# RefOsc10MHz_1V3.net
KiCad netlist of a schematic drawn in EAGLE
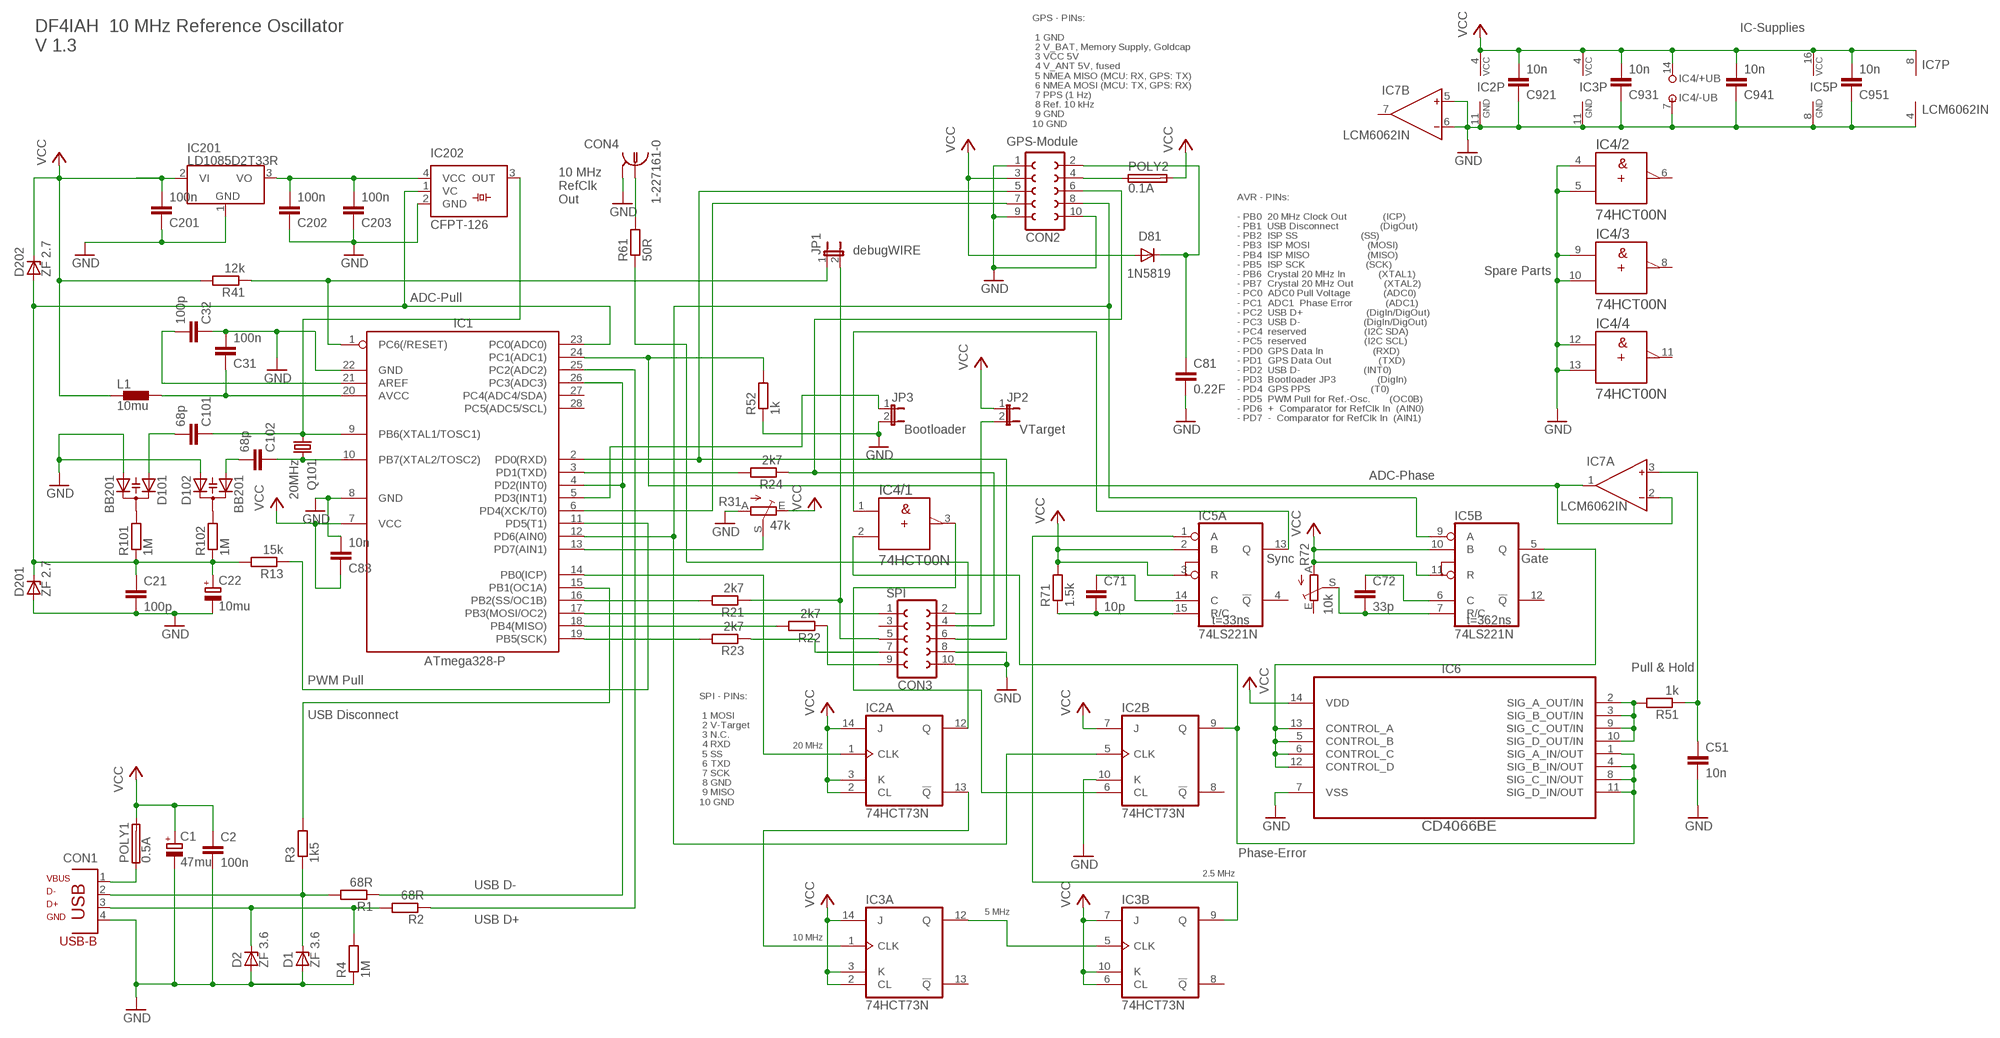
[diagram p0: schematic, sheet 1]

(export (version "E")
  (design (tool "Eeschema 10.0.6"))
  (components
    (comp (ref "C1")
      (value "47mu")
      (footprint "eagle-import:E2-4")
      (libsource (lib "eagle-import") (part "CPOL-EUE2-4"))
    )
    (comp (ref "C2")
      (value "100n")
      (footprint "eagle-import:C5B3")
      (libsource (lib "eagle-import") (part "C5/3"))
    )
    (comp (ref "C21")
      (value "100p")
      (footprint "eagle-import:C5B3")
      (libsource (lib "eagle-import") (part "C5/3"))
    )
    (comp (ref "C22")
      (value "10mu")
      (footprint "eagle-import:E2-4")
      (libsource (lib "eagle-import") (part "CPOL-EUE2-4"))
    )
    (comp (ref "C31")
      (value "100n")
      (footprint "eagle-import:C5B3")
      (libsource (lib "eagle-import") (part "C5/3"))
    )
    (comp (ref "C32")
      (value "100p")
      (footprint "eagle-import:C5B3")
      (libsource (lib "eagle-import") (part "C5/3"))
    )
    (comp (ref "C51")
      (value "10n")
      (footprint "eagle-import:C5B3")
      (libsource (lib "eagle-import") (part "C5/3"))
    )
    (comp (ref "C71")
      (value "10p")
      (footprint "eagle-import:C5B3")
      (libsource (lib "eagle-import") (part "C5/3"))
    )
    (comp (ref "C72")
      (value "33p")
      (footprint "eagle-import:C5B3")
      (libsource (lib "eagle-import") (part "C5/3"))
    )
    (comp (ref "C81")
      (value "0.22F")
      (footprint "eagle-import:C5B7.2")
      (libsource (lib "eagle-import") (part "C5/7.2"))
    )
    (comp (ref "C83")
      (value "10n")
      (footprint "eagle-import:C5B3")
      (libsource (lib "eagle-import") (part "C5/3"))
    )
    (comp (ref "C101")
      (value "68p")
      (footprint "eagle-import:C5B3")
      (libsource (lib "eagle-import") (part "C5/3"))
    )
    (comp (ref "C102")
      (value "68p")
      (footprint "eagle-import:C5B3")
      (libsource (lib "eagle-import") (part "C5/3"))
    )
    (comp (ref "C201")
      (value "100n")
      (footprint "eagle-import:C5B3")
      (libsource (lib "eagle-import") (part "C5/3"))
    )
    (comp (ref "C202")
      (value "100n")
      (footprint "eagle-import:C5B3")
      (libsource (lib "eagle-import") (part "C5/3"))
    )
    (comp (ref "C203")
      (value "100n")
      (footprint "eagle-import:C5B3")
      (libsource (lib "eagle-import") (part "C5/3"))
    )
    (comp (ref "C921")
      (value "10n")
      (footprint "eagle-import:C5B3")
      (libsource (lib "eagle-import") (part "C5/3"))
    )
    (comp (ref "C931")
      (value "10n")
      (footprint "eagle-import:C5B3")
      (libsource (lib "eagle-import") (part "C5/3"))
    )
    (comp (ref "C941")
      (value "10n")
      (footprint "eagle-import:C5B3")
      (libsource (lib "eagle-import") (part "C5/3"))
    )
    (comp (ref "C951")
      (value "10n")
      (footprint "eagle-import:C5B3")
      (libsource (lib "eagle-import") (part "C5/3"))
    )
    (comp (ref "CON1")
      (value "PN61729")
      (footprint "eagle-import:PN61729")
      (libsource (lib "eagle-import") (part "PN61729"))
    )
    (comp (ref "CON2")
      (value "FE05-2")
      (footprint "eagle-import:FE05-2")
      (libsource (lib "eagle-import") (part "FE05-2"))
    )
    (comp (ref "CON3")
      (value "FE05-2")
      (footprint "eagle-import:FE05-2")
      (libsource (lib "eagle-import") (part "FE05-2"))
    )
    (comp (ref "CON4")
      (value "1-227161-0")
      (footprint "eagle-import:AMP_227161")
      (fields (field (name "MF") "TYCO ELECTRONICS") (field (name "MPN") "1-227161"))
      (libsource (lib "eagle-import") (part "?2271611--0"))
    )
    (comp (ref "D1")
      (value "ZF 3.6")
      (footprint "eagle-import:DO41Z10")
      (libsource (lib "eagle-import") (part "1N4728"))
    )
    (comp (ref "D2")
      (value "ZF 3.6")
      (footprint "eagle-import:DO41Z10")
      (libsource (lib "eagle-import") (part "1N4728"))
    )
    (comp (ref "D81")
      (value "1N5819")
      (footprint "eagle-import:DO41-10")
      (libsource (lib "eagle-import") (part "1N4942"))
    )
    (comp (ref "D101")
      (value "BB201")
      (footprint "eagle-import:SOT23")
      (libsource (lib "eagle-import") (part "BBY51"))
    )
    (comp (ref "D102")
      (value "BB201")
      (footprint "eagle-import:SOT23")
      (libsource (lib "eagle-import") (part "BBY51"))
    )
    (comp (ref "D201")
      (value "ZF 2.7")
      (footprint "eagle-import:DO41Z10")
      (libsource (lib "eagle-import") (part "1N4728"))
    )
    (comp (ref "D202")
      (value "ZF 2.7")
      (footprint "eagle-import:DO41Z10")
      (libsource (lib "eagle-import") (part "1N4728"))
    )
    (comp (ref "IC1")
      (value "ATmega328-P")
      (footprint "eagle-import:DIL28-3")
      (libsource (lib "eagle-import") (part "MEGA8-P"))
    )
    (comp (ref "IC2")
      (value "74HCT73N")
      (footprint "eagle-import:DIL14")
      (libsource (lib "eagle-import") (part "7473NLS"))
    )
    (comp (ref "IC3")
      (value "74HCT73N")
      (footprint "eagle-import:DIL14")
      (libsource (lib "eagle-import") (part "7473NLS"))
    )
    (comp (ref "IC4")
      (value "74HCT00N")
      (footprint "eagle-import:DIL14")
      (libsource (lib "eagle-import") (part "7400NHCT"))
    )
    (comp (ref "IC5")
      (value "74LS221N")
      (footprint "eagle-import:DIL16")
      (libsource (lib "eagle-import") (part "74221NLS"))
    )
    (comp (ref "IC6")
      (value "CD4066BE")
      (footprint "eagle-import:DIP254P762X508-14")
      (libsource (lib "eagle-import") (part "CD4066BE"))
    )
    (comp (ref "IC7")
      (value "LCM6062IN")
      (footprint "eagle-import:DIL08")
      (libsource (lib "eagle-import") (part "AD822IN"))
    )
    (comp (ref "IC201")
      (value "LD10853.3")
      (footprint "eagle-import:TO220V")
      (libsource (lib "eagle-import") (part "LD10853.3"))
    )
    (comp (ref "IC202")
      (value "CFPT-126")
      (footprint "eagle-import:SM77H")
      (libsource (lib "eagle-import") (part "CFPT-126"))
    )
    (comp (ref "JP1")
      (value "JP1E")
      (footprint "eagle-import:JP1")
      (libsource (lib "eagle-import") (part "JP1E"))
    )
    (comp (ref "JP2")
      (value "JP1E")
      (footprint "eagle-import:JP1")
      (libsource (lib "eagle-import") (part "JP1E"))
    )
    (comp (ref "JP3")
      (value "JP1E")
      (footprint "eagle-import:JP1")
      (libsource (lib "eagle-import") (part "JP1E"))
    )
    (comp (ref "L1")
      (value "10mu")
      (footprint "eagle-import:BL01RN1A")
      (libsource (lib "eagle-import") (part "BL01RN1A"))
    )
    (comp (ref "POLY1")
      (value "0.5A")
      (footprint "eagle-import:TE5")
      (libsource (lib "eagle-import") (part "FUSETE5"))
    )
    (comp (ref "POLY2")
      (value "0.1A")
      (footprint "eagle-import:TE5")
      (libsource (lib "eagle-import") (part "FUSETE5"))
    )
    (comp (ref "Q101")
      (value "20MHz")
      (footprint "eagle-import:HC49U70")
      (libsource (lib "eagle-import") (part "CRYSTALHC49U70"))
    )
    (comp (ref "R1")
      (value "68R")
      (footprint "eagle-import:0204_7")
      (libsource (lib "eagle-import") (part "R-EU_0204/7"))
    )
    (comp (ref "R2")
      (value "68R")
      (footprint "eagle-import:0204_7")
      (libsource (lib "eagle-import") (part "R-EU_0204/7"))
    )
    (comp (ref "R3")
      (value "1k5")
      (footprint "eagle-import:0204_7")
      (libsource (lib "eagle-import") (part "R-EU_0204/7"))
    )
    (comp (ref "R4")
      (value "1M")
      (footprint "eagle-import:0204_7")
      (libsource (lib "eagle-import") (part "R-EU_0204/7"))
    )
    (comp (ref "R13")
      (value "15k")
      (footprint "eagle-import:0204_7")
      (libsource (lib "eagle-import") (part "R-EU_0204/7"))
    )
    (comp (ref "R21")
      (value "2k7")
      (footprint "eagle-import:0204_7")
      (libsource (lib "eagle-import") (part "R-EU_0204/7"))
    )
    (comp (ref "R22")
      (value "2k7")
      (footprint "eagle-import:0204_7")
      (libsource (lib "eagle-import") (part "R-EU_0204/7"))
    )
    (comp (ref "R23")
      (value "2k7")
      (footprint "eagle-import:0204_7")
      (libsource (lib "eagle-import") (part "R-EU_0204/7"))
    )
    (comp (ref "R24")
      (value "2k7")
      (footprint "eagle-import:0204_7")
      (libsource (lib "eagle-import") (part "R-EU_0204/7"))
    )
    (comp (ref "R31")
      (value "47k")
      (footprint "eagle-import:S64YW")
      (libsource (lib "eagle-import") (part "TRIM_1234-S64YW"))
    )
    (comp (ref "R41")
      (value "12k")
      (footprint "eagle-import:0204_7")
      (libsource (lib "eagle-import") (part "R-EU_0204/7"))
    )
    (comp (ref "R51")
      (value "1k")
      (footprint "eagle-import:0204_7")
      (libsource (lib "eagle-import") (part "R-EU_0204/7"))
    )
    (comp (ref "R52")
      (value "1k")
      (footprint "eagle-import:0204_7")
      (libsource (lib "eagle-import") (part "R-EU_0204/7"))
    )
    (comp (ref "R61")
      (value "50R")
      (footprint "eagle-import:0204_7")
      (libsource (lib "eagle-import") (part "R-EU_0204/7"))
    )
    (comp (ref "R71")
      (value "1.5k")
      (footprint "eagle-import:0204_7")
      (libsource (lib "eagle-import") (part "R-EU_0204/7"))
    )
    (comp (ref "R72")
      (value "10k")
      (footprint "eagle-import:S64YW")
      (libsource (lib "eagle-import") (part "TRIM_1234-S64YW"))
    )
    (comp (ref "R101")
      (value "1M")
      (footprint "eagle-import:0204_7")
      (libsource (lib "eagle-import") (part "R-EU_0204/7"))
    )
    (comp (ref "R102")
      (value "1M")
      (footprint "eagle-import:0204_7")
      (libsource (lib "eagle-import") (part "R-EU_0204/7"))
    )
  )
  (nets
    (net (code "1") (name "GND") (class "Default")
      (node (ref "C1") (pin "-") (pinfunction "-_-") (pintype "passive"))
      (node (ref "C2") (pin "2") (pinfunction "2_2") (pintype "passive"))
      (node (ref "C201") (pin "1") (pinfunction "1_1") (pintype "passive"))
      (node (ref "C202") (pin "1") (pinfunction "1_1") (pintype "passive"))
      (node (ref "C203") (pin "1") (pinfunction "1_1") (pintype "passive"))
      (node (ref "C21") (pin "2") (pinfunction "2_2") (pintype "passive"))
      (node (ref "C22") (pin "-") (pinfunction "-_-") (pintype "passive"))
      (node (ref "C31") (pin "2") (pinfunction "2_2") (pintype "passive"))
      (node (ref "C32") (pin "1") (pinfunction "1_1") (pintype "passive"))
      (node (ref "C51") (pin "2") (pinfunction "2_2") (pintype "passive"))
      (node (ref "C81") (pin "2") (pinfunction "2_2") (pintype "passive"))
      (node (ref "C83") (pin "2") (pinfunction "2_2") (pintype "passive"))
      (node (ref "C921") (pin "1") (pinfunction "1_1") (pintype "passive"))
      (node (ref "C931") (pin "1") (pinfunction "1_1") (pintype "passive"))
      (node (ref "C941") (pin "1") (pinfunction "1_1") (pintype "passive"))
      (node (ref "C951") (pin "1") (pinfunction "1_1") (pintype "passive"))
      (node (ref "CON1") (pin "4") (pinfunction "4_4") (pintype "passive"))
      (node (ref "CON2") (pin "1") (pinfunction "1_1") (pintype "passive"))
      (node (ref "CON2") (pin "10") (pinfunction "10_10") (pintype "passive"))
      (node (ref "CON2") (pin "9") (pinfunction "9_9") (pintype "passive"))
      (node (ref "CON3") (pin "10") (pinfunction "10_10") (pintype "passive"))
      (node (ref "CON3") (pin "8") (pinfunction "8_8") (pintype "passive"))
      (node (ref "CON4") (pin "2") (pinfunction "2_2") (pintype "passive"))
      (node (ref "D1") (pin "A") (pinfunction "A_A") (pintype "passive"))
      (node (ref "D101") (pin "2") (pinfunction "A2_2") (pintype "passive"))
      (node (ref "D102") (pin "1") (pinfunction "A1_1") (pintype "passive"))
      (node (ref "D2") (pin "A") (pinfunction "A_A") (pintype "passive"))
      (node (ref "D201") (pin "A") (pinfunction "A_A") (pintype "passive"))
      (node (ref "IC1") (pin "22") (pinfunction "GND_22") (pintype "power_in"))
      (node (ref "IC1") (pin "8") (pinfunction "GND_8") (pintype "power_in"))
      (node (ref "IC2") (pin "10") (pinfunction "K_10") (pintype "input"))
      (node (ref "IC2") (pin "11") (pinfunction "GND_11") (pintype "power_in"))
      (node (ref "IC201") (pin "1") (pinfunction "GND_1") (pintype "passive"))
      (node (ref "IC202") (pin "2") (pinfunction "GND_2") (pintype "power_in"))
      (node (ref "IC3") (pin "11") (pinfunction "GND_11") (pintype "power_in"))
      (node (ref "IC4") (pin "10") (pinfunction "B_10") (pintype "input"))
      (node (ref "IC4") (pin "12") (pinfunction "A_12") (pintype "input"))
      (node (ref "IC4") (pin "13") (pinfunction "B_13") (pintype "input"))
      (node (ref "IC4") (pin "4") (pinfunction "A_4") (pintype "input"))
      (node (ref "IC4") (pin "5") (pinfunction "B_5") (pintype "input"))
      (node (ref "IC4") (pin "7") (pinfunction "-UB_7") (pintype "power_in"))
      (node (ref "IC4") (pin "9") (pinfunction "A_9") (pintype "input"))
      (node (ref "IC5") (pin "8") (pinfunction "GND_8") (pintype "power_in"))
      (node (ref "IC6") (pin "7") (pinfunction "VSS_7") (pintype "passive"))
      (node (ref "IC7") (pin "4") (pinfunction "V-_4") (pintype "power_in"))
      (node (ref "IC7") (pin "5") (pinfunction "IN+_5") (pintype "input"))
      (node (ref "IC7") (pin "6") (pinfunction "IN-_6") (pintype "input"))
      (node (ref "JP3") (pin "2") (pinfunction "2_2") (pintype "passive"))
      (node (ref "R31") (pin "A") (pinfunction "A_A") (pintype "passive"))
      (node (ref "R4") (pin "1") (pinfunction "1_1") (pintype "passive"))
      (node (ref "R52") (pin "1") (pinfunction "1_1") (pintype "passive"))
    )
    (net (code "2") (name "Net-(C81-Pad1)") (class "Default")
      (node (ref "C81") (pin "1") (pinfunction "1_1") (pintype "passive"))
      (node (ref "CON2") (pin "2") (pinfunction "2_2") (pintype "passive"))
      (node (ref "D81") (pin "C") (pinfunction "C_C") (pintype "passive"))
    )
    (net (code "3") (name "Net-(CON1-Pad1)") (class "Default")
      (node (ref "CON1") (pin "1") (pinfunction "1_1") (pintype "passive"))
      (node (ref "POLY1") (pin "1") (pinfunction "1_1") (pintype "passive"))
    )
    (net (code "4") (name "Net-(CON1-Pad2)") (class "Default")
      (node (ref "CON1") (pin "2") (pinfunction "2_2") (pintype "passive"))
      (node (ref "D1") (pin "C") (pinfunction "C_C") (pintype "passive"))
      (node (ref "R1") (pin "2") (pinfunction "2_2") (pintype "passive"))
      (node (ref "R3") (pin "1") (pinfunction "1_1") (pintype "passive"))
    )
    (net (code "5") (name "Net-(CON1-Pad3)") (class "Default")
      (node (ref "CON1") (pin "3") (pinfunction "3_3") (pintype "passive"))
      (node (ref "D2") (pin "C") (pinfunction "C_C") (pintype "passive"))
      (node (ref "R2") (pin "2") (pinfunction "2_2") (pintype "passive"))
      (node (ref "R4") (pin "2") (pinfunction "2_2") (pintype "passive"))
    )
    (net (code "6") (name "Net-(CON2-Pad4)") (class "Default")
      (node (ref "CON2") (pin "4") (pinfunction "4_4") (pintype "passive"))
      (node (ref "POLY2") (pin "1") (pinfunction "1_1") (pintype "passive"))
    )
    (net (code "7") (name "Net-(CON2-Pad6)") (class "Default")
      (node (ref "CON2") (pin "6") (pinfunction "6_6") (pintype "passive"))
      (node (ref "CON3") (pin "4") (pinfunction "4_4") (pintype "passive"))
      (node (ref "R24") (pin "1") (pinfunction "1_1") (pintype "passive"))
    )
    (net (code "8") (name "Net-(CON3-Pad2)") (class "Default")
      (node (ref "CON3") (pin "2") (pinfunction "2_2") (pintype "passive"))
      (node (ref "JP2") (pin "2") (pinfunction "2_2") (pintype "passive"))
    )
    (net (code "9") (name "Net-(CON3-Pad5)") (class "Default")
      (node (ref "CON3") (pin "5") (pinfunction "5_5") (pintype "passive"))
      (node (ref "JP1") (pin "2") (pinfunction "2_2") (pintype "passive"))
      (node (ref "R21") (pin "1") (pinfunction "1_1") (pintype "passive"))
    )
    (net (code "10") (name "Net-(CON3-Pad7)") (class "Default")
      (node (ref "CON3") (pin "7") (pinfunction "7_7") (pintype "passive"))
      (node (ref "R23") (pin "1") (pinfunction "1_1") (pintype "passive"))
    )
    (net (code "11") (name "Net-(CON3-Pad9)") (class "Default")
      (node (ref "CON3") (pin "9") (pinfunction "9_9") (pintype "passive"))
      (node (ref "R22") (pin "1") (pinfunction "1_1") (pintype "passive"))
    )
    (net (code "12") (name "Net-(CON4-Pad1)") (class "Default")
      (node (ref "CON4") (pin "1") (pinfunction "1_1") (pintype "passive"))
      (node (ref "R61") (pin "2") (pinfunction "2_2") (pintype "passive"))
    )
    (net (code "13") (name "Net-(D101-A1)") (class "Default")
      (node (ref "C101") (pin "2") (pinfunction "2_2") (pintype "passive"))
      (node (ref "D101") (pin "1") (pinfunction "A1_1") (pintype "passive"))
    )
    (net (code "14") (name "Net-(D101-C)") (class "Default")
      (node (ref "D101") (pin "3") (pinfunction "C_3") (pintype "passive"))
      (node (ref "R101") (pin "2") (pinfunction "2_2") (pintype "passive"))
    )
    (net (code "15") (name "Net-(D102-A2)") (class "Default")
      (node (ref "C102") (pin "2") (pinfunction "2_2") (pintype "passive"))
      (node (ref "D102") (pin "2") (pinfunction "A2_2") (pintype "passive"))
    )
    (net (code "16") (name "Net-(D102-C)") (class "Default")
      (node (ref "D102") (pin "3") (pinfunction "C_3") (pintype "passive"))
      (node (ref "R102") (pin "2") (pinfunction "2_2") (pintype "passive"))
    )
    (net (code "17") (name "Net-(IC1-AREF)") (class "Default")
      (node (ref "C32") (pin "2") (pinfunction "2_2") (pintype "passive"))
      (node (ref "IC1") (pin "21") (pinfunction "AREF_21") (pintype "passive"))
    )
    (net (code "18") (name "Net-(IC1-AVCC)") (class "Default")
      (node (ref "C31") (pin "1") (pinfunction "1_1") (pintype "passive"))
      (node (ref "IC1") (pin "20") (pinfunction "AVCC_20") (pintype "power_in"))
      (node (ref "L1") (pin "2") (pinfunction "2_2") (pintype "passive"))
    )
    (net (code "19") (name "Net-(IC1-PB0(ICP))") (class "Default")
      (node (ref "IC1") (pin "14") (pinfunction "PB0(ICP)_14") (pintype "bidirectional"))
      (node (ref "IC2") (pin "1") (pinfunction "CLK_1") (pintype "input"))
    )
    (net (code "20") (name "Net-(IC1-PB1(OC1A))") (class "Default")
      (node (ref "IC1") (pin "15") (pinfunction "PB1(OC1A)_15") (pintype "bidirectional"))
      (node (ref "R3") (pin "2") (pinfunction "2_2") (pintype "passive"))
    )
    (net (code "21") (name "Net-(IC1-PB2(SS{slash}OC1B))") (class "Default")
      (node (ref "IC1") (pin "16") (pinfunction "PB2(SS/OC1B)_16") (pintype "bidirectional"))
      (node (ref "R21") (pin "2") (pinfunction "2_2") (pintype "passive"))
    )
    (net (code "22") (name "Net-(IC1-PB3(MOSI{slash}OC2))") (class "Default")
      (node (ref "CON3") (pin "1") (pinfunction "1_1") (pintype "passive"))
      (node (ref "IC1") (pin "17") (pinfunction "PB3(MOSI/OC2)_17") (pintype "bidirectional"))
    )
    (net (code "23") (name "Net-(IC1-PB4(MISO))") (class "Default")
      (node (ref "IC1") (pin "18") (pinfunction "PB4(MISO)_18") (pintype "bidirectional"))
      (node (ref "R22") (pin "2") (pinfunction "2_2") (pintype "passive"))
    )
    (net (code "24") (name "Net-(IC1-PB5(SCK))") (class "Default")
      (node (ref "IC1") (pin "19") (pinfunction "PB5(SCK)_19") (pintype "bidirectional"))
      (node (ref "R23") (pin "2") (pinfunction "2_2") (pintype "passive"))
    )
    (net (code "25") (name "Net-(IC1-PB6(XTAL1{slash}TOSC1))") (class "Default")
      (node (ref "C101") (pin "1") (pinfunction "1_1") (pintype "passive"))
      (node (ref "IC1") (pin "9") (pinfunction "PB6(XTAL1/TOSC1)_9") (pintype "bidirectional"))
      (node (ref "IC202") (pin "3") (pinfunction "OUT_3") (pintype "output"))
      (node (ref "Q101") (pin "1") (pinfunction "1_1") (pintype "passive"))
    )
    (net (code "26") (name "Net-(IC1-PB7(XTAL2{slash}TOSC2))") (class "Default")
      (node (ref "C102") (pin "1") (pinfunction "1_1") (pintype "passive"))
      (node (ref "IC1") (pin "10") (pinfunction "PB7(XTAL2/TOSC2)_10") (pintype "bidirectional"))
      (node (ref "Q101") (pin "2") (pinfunction "2_2") (pintype "passive"))
    )
    (net (code "27") (name "Net-(IC1-PC0(ADC0))") (class "Default")
      (node (ref "C21") (pin "1") (pinfunction "1_1") (pintype "passive"))
      (node (ref "C22") (pin "+") (pinfunction "+_+") (pintype "passive"))
      (node (ref "D201") (pin "C") (pinfunction "C_C") (pintype "passive"))
      (node (ref "D202") (pin "A") (pinfunction "A_A") (pintype "passive"))
      (node (ref "IC1") (pin "23") (pinfunction "PC0(ADC0)_23") (pintype "bidirectional"))
      (node (ref "IC202") (pin "1") (pinfunction "VC_1") (pintype "input"))
      (node (ref "R101") (pin "1") (pinfunction "1_1") (pintype "passive"))
      (node (ref "R102") (pin "1") (pinfunction "1_1") (pintype "passive"))
      (node (ref "R13") (pin "2") (pinfunction "2_2") (pintype "passive"))
    )
    (net (code "28") (name "Net-(IC1-PC1(ADC1))") (class "Default")
      (node (ref "IC1") (pin "24") (pinfunction "PC1(ADC1)_24") (pintype "bidirectional"))
      (node (ref "IC7") (pin "1") (pinfunction "OUT_1") (pintype "output"))
      (node (ref "IC7") (pin "2") (pinfunction "IN-_2") (pintype "input"))
      (node (ref "R52") (pin "2") (pinfunction "2_2") (pintype "passive"))
    )
    (net (code "29") (name "Net-(IC1-PC2(ADC2))") (class "Default")
      (node (ref "IC1") (pin "25") (pinfunction "PC2(ADC2)_25") (pintype "bidirectional"))
      (node (ref "R2") (pin "1") (pinfunction "1_1") (pintype "passive"))
    )
    (net (code "30") (name "Net-(IC1-PC3(ADC3))") (class "Default")
      (node (ref "IC1") (pin "26") (pinfunction "PC3(ADC3)_26") (pintype "bidirectional"))
      (node (ref "IC1") (pin "4") (pinfunction "PD2(INT0)_4") (pintype "bidirectional"))
      (node (ref "R1") (pin "1") (pinfunction "1_1") (pintype "passive"))
    )
    (net (code "31") (name "Net-(IC1-PC6({slash}RESET))") (class "Default")
      (node (ref "IC1") (pin "1") (pinfunction "PC6(/RESET)_1") (pintype "bidirectional"))
      (node (ref "JP1") (pin "1") (pinfunction "1_1") (pintype "passive"))
      (node (ref "R41") (pin "1") (pinfunction "1_1") (pintype "passive"))
    )
    (net (code "32") (name "Net-(IC1-PD0(RXD))") (class "Default")
      (node (ref "CON2") (pin "5") (pinfunction "5_5") (pintype "passive"))
      (node (ref "CON3") (pin "6") (pinfunction "6_6") (pintype "passive"))
      (node (ref "IC1") (pin "2") (pinfunction "PD0(RXD)_2") (pintype "bidirectional"))
    )
    (net (code "33") (name "Net-(IC1-PD1(TXD))") (class "Default")
      (node (ref "IC1") (pin "3") (pinfunction "PD1(TXD)_3") (pintype "bidirectional"))
      (node (ref "R24") (pin "2") (pinfunction "2_2") (pintype "passive"))
    )
    (net (code "34") (name "Net-(IC1-PD3(INT1))") (class "Default")
      (node (ref "IC1") (pin "5") (pinfunction "PD3(INT1)_5") (pintype "bidirectional"))
      (node (ref "JP3") (pin "1") (pinfunction "1_1") (pintype "passive"))
    )
    (net (code "35") (name "Net-(IC1-PD4(XCK{slash}T0))") (class "Default")
      (node (ref "CON2") (pin "7") (pinfunction "7_7") (pintype "passive"))
      (node (ref "IC1") (pin "6") (pinfunction "PD4(XCK/T0)_6") (pintype "bidirectional"))
    )
    (net (code "36") (name "Net-(IC1-PD5(T1))") (class "Default")
      (node (ref "IC1") (pin "11") (pinfunction "PD5(T1)_11") (pintype "bidirectional"))
      (node (ref "R13") (pin "1") (pinfunction "1_1") (pintype "passive"))
    )
    (net (code "37") (name "Net-(IC1-PD6(AIN0))") (class "Default")
      (node (ref "CON2") (pin "8") (pinfunction "8_8") (pintype "passive"))
      (node (ref "IC1") (pin "12") (pinfunction "PD6(AIN0)_12") (pintype "bidirectional"))
      (node (ref "IC2") (pin "5") (pinfunction "CLK_5") (pintype "input"))
      (node (ref "IC5") (pin "9") (pinfunction "A_9") (pintype "input"))
    )
    (net (code "38") (name "Net-(IC1-PD7(AIN1))") (class "Default")
      (node (ref "IC1") (pin "13") (pinfunction "PD7(AIN1)_13") (pintype "bidirectional"))
      (node (ref "R31") (pin "S") (pinfunction "S_S") (pintype "passive"))
    )
    (net (code "39") (name "Net-(IC2A-Q)") (class "Default")
      (node (ref "IC2") (pin "12") (pinfunction "Q_12") (pintype "output"))
      (node (ref "R61") (pin "1") (pinfunction "1_1") (pintype "passive"))
    )
    (net (code "40") (name "Net-(IC2A-~{Q})") (class "Default")
      (node (ref "IC2") (pin "13") (pinfunction "~{Q}_13") (pintype "output"))
      (node (ref "IC3") (pin "1") (pinfunction "CLK_1") (pintype "input"))
    )
    (net (code "41") (name "Net-(IC2B-CL)") (class "Default")
      (node (ref "IC2") (pin "6") (pinfunction "CL_6") (pintype "input"))
      (node (ref "IC4") (pin "3") (pinfunction "Y_3") (pintype "output"))
    )
    (net (code "42") (name "Net-(IC2B-Q)") (class "Default")
      (node (ref "IC2") (pin "9") (pinfunction "Q_9") (pintype "output"))
      (node (ref "IC4") (pin "2") (pinfunction "B_2") (pintype "input"))
      (node (ref "IC6") (pin "1") (pinfunction "SIG_A_IN/OUT_1") (pintype "bidirectional"))
      (node (ref "IC6") (pin "11") (pinfunction "SIG_D_IN/OUT_11") (pintype "bidirectional"))
      (node (ref "IC6") (pin "4") (pinfunction "SIG_B_IN/OUT_4") (pintype "bidirectional"))
      (node (ref "IC6") (pin "8") (pinfunction "SIG_C_IN/OUT_8") (pintype "bidirectional"))
    )
    (net (code "43") (name "Net-(IC3A-Q)") (class "Default")
      (node (ref "IC3") (pin "12") (pinfunction "Q_12") (pintype "output"))
      (node (ref "IC3") (pin "5") (pinfunction "CLK_5") (pintype "input"))
    )
    (net (code "44") (name "Net-(IC3B-Q)") (class "Default")
      (node (ref "IC3") (pin "9") (pinfunction "Q_9") (pintype "output"))
      (node (ref "IC5") (pin "1") (pinfunction "A_1") (pintype "input"))
    )
    (net (code "45") (name "Net-(IC4C-A)") (class "Default")
      (node (ref "IC4") (pin "1") (pinfunction "A_1") (pintype "input"))
      (node (ref "IC5") (pin "13") (pinfunction "Q_13") (pintype "output"))
    )
    (net (code "46") (name "Net-(IC5A-C)") (class "Default")
      (node (ref "C71") (pin "1") (pinfunction "1_1") (pintype "passive"))
      (node (ref "IC5") (pin "14") (pinfunction "C_14") (pintype "input"))
    )
    (net (code "47") (name "Net-(IC5A-R{slash}C)") (class "Default")
      (node (ref "C71") (pin "2") (pinfunction "2_2") (pintype "passive"))
      (node (ref "IC5") (pin "15") (pinfunction "R/C_15") (pintype "input"))
      (node (ref "R71") (pin "1") (pinfunction "1_1") (pintype "passive"))
    )
    (net (code "48") (name "Net-(IC5B-C)") (class "Default")
      (node (ref "C72") (pin "1") (pinfunction "1_1") (pintype "passive"))
      (node (ref "IC5") (pin "6") (pinfunction "C_6") (pintype "input"))
    )
    (net (code "49") (name "Net-(IC5B-Q)") (class "Default")
      (node (ref "IC5") (pin "5") (pinfunction "Q_5") (pintype "output"))
      (node (ref "IC6") (pin "12") (pinfunction "CONTROL_D_12") (pintype "input"))
      (node (ref "IC6") (pin "13") (pinfunction "CONTROL_A_13") (pintype "input"))
      (node (ref "IC6") (pin "5") (pinfunction "CONTROL_B_5") (pintype "input"))
      (node (ref "IC6") (pin "6") (pinfunction "CONTROL_C_6") (pintype "input"))
    )
    (net (code "50") (name "Net-(IC5B-R{slash}C)") (class "Default")
      (node (ref "C72") (pin "2") (pinfunction "2_2") (pintype "passive"))
      (node (ref "IC5") (pin "7") (pinfunction "R/C_7") (pintype "input"))
      (node (ref "R72") (pin "S") (pinfunction "S_S") (pintype "passive"))
    )
    (net (code "51") (name "Net-(IC6-SIG_A_OUT{slash}IN)") (class "Default")
      (node (ref "IC6") (pin "10") (pinfunction "SIG_D_OUT/IN_10") (pintype "bidirectional"))
      (node (ref "IC6") (pin "2") (pinfunction "SIG_A_OUT/IN_2") (pintype "bidirectional"))
      (node (ref "IC6") (pin "3") (pinfunction "SIG_B_OUT/IN_3") (pintype "bidirectional"))
      (node (ref "IC6") (pin "9") (pinfunction "SIG_C_OUT/IN_9") (pintype "bidirectional"))
      (node (ref "R51") (pin "2") (pinfunction "2_2") (pintype "passive"))
    )
    (net (code "52") (name "Net-(IC7A-IN+)") (class "Default")
      (node (ref "C51") (pin "1") (pinfunction "1_1") (pintype "passive"))
      (node (ref "IC7") (pin "3") (pinfunction "IN+_3") (pintype "input"))
      (node (ref "R51") (pin "1") (pinfunction "1_1") (pintype "passive"))
    )
    (net (code "53") (name "Net-(IC201-VO)") (class "Default")
      (node (ref "C202") (pin "2") (pinfunction "2_2") (pintype "passive"))
      (node (ref "C203") (pin "2") (pinfunction "2_2") (pintype "passive"))
      (node (ref "IC201") (pin "3") (pinfunction "VO_3") (pintype "passive"))
      (node (ref "IC202") (pin "4") (pinfunction "VCC_4") (pintype "power_in"))
    )
    (net (code "54") (name "VCC") (class "Default")
      (node (ref "C1") (pin "+") (pinfunction "+_+") (pintype "passive"))
      (node (ref "C2") (pin "1") (pinfunction "1_1") (pintype "passive"))
      (node (ref "C201") (pin "2") (pinfunction "2_2") (pintype "passive"))
      (node (ref "C83") (pin "1") (pinfunction "1_1") (pintype "passive"))
      (node (ref "C921") (pin "2") (pinfunction "2_2") (pintype "passive"))
      (node (ref "C931") (pin "2") (pinfunction "2_2") (pintype "passive"))
      (node (ref "C941") (pin "2") (pinfunction "2_2") (pintype "passive"))
      (node (ref "C951") (pin "2") (pinfunction "2_2") (pintype "passive"))
      (node (ref "CON2") (pin "3") (pinfunction "3_3") (pintype "passive"))
      (node (ref "D202") (pin "C") (pinfunction "C_C") (pintype "passive"))
      (node (ref "D81") (pin "A") (pinfunction "A_A") (pintype "passive"))
      (node (ref "IC1") (pin "7") (pinfunction "VCC_7") (pintype "power_in"))
      (node (ref "IC2") (pin "14") (pinfunction "J_14") (pintype "input"))
      (node (ref "IC2") (pin "2") (pinfunction "CL_2") (pintype "input"))
      (node (ref "IC2") (pin "3") (pinfunction "K_3") (pintype "input"))
      (node (ref "IC2") (pin "4") (pinfunction "VCC_4") (pintype "power_in"))
      (node (ref "IC2") (pin "7") (pinfunction "J_7") (pintype "input"))
      (node (ref "IC201") (pin "2") (pinfunction "VI_2") (pintype "input"))
      (node (ref "IC3") (pin "10") (pinfunction "K_10") (pintype "input"))
      (node (ref "IC3") (pin "14") (pinfunction "J_14") (pintype "input"))
      (node (ref "IC3") (pin "2") (pinfunction "CL_2") (pintype "input"))
      (node (ref "IC3") (pin "3") (pinfunction "K_3") (pintype "input"))
      (node (ref "IC3") (pin "4") (pinfunction "VCC_4") (pintype "power_in"))
      (node (ref "IC3") (pin "6") (pinfunction "CL_6") (pintype "input"))
      (node (ref "IC3") (pin "7") (pinfunction "J_7") (pintype "input"))
      (node (ref "IC4") (pin "14") (pinfunction "+UB_14") (pintype "power_in"))
      (node (ref "IC5") (pin "10") (pinfunction "B_10") (pintype "input"))
      (node (ref "IC5") (pin "11") (pinfunction "R_11") (pintype "input"))
      (node (ref "IC5") (pin "16") (pinfunction "VCC_16") (pintype "power_in"))
      (node (ref "IC5") (pin "2") (pinfunction "B_2") (pintype "input"))
      (node (ref "IC5") (pin "3") (pinfunction "R_3") (pintype "input"))
      (node (ref "IC6") (pin "14") (pinfunction "VDD_14") (pintype "power_in"))
      (node (ref "IC7") (pin "8") (pinfunction "V+_8") (pintype "power_in"))
      (node (ref "JP2") (pin "1") (pinfunction "1_1") (pintype "passive"))
      (node (ref "L1") (pin "1") (pinfunction "1_1") (pintype "passive"))
      (node (ref "POLY1") (pin "2") (pinfunction "2_2") (pintype "passive"))
      (node (ref "POLY2") (pin "2") (pinfunction "2_2") (pintype "passive"))
      (node (ref "R31") (pin "E") (pinfunction "E_E") (pintype "passive"))
      (node (ref "R41") (pin "2") (pinfunction "2_2") (pintype "passive"))
      (node (ref "R71") (pin "2") (pinfunction "2_2") (pintype "passive"))
      (node (ref "R72") (pin "A") (pinfunction "A_A") (pintype "passive"))
    )
    (net (code "55") (name "unconnected-(CON3-Pad3)") (class "Default")
      (node (ref "CON3") (pin "3") (pinfunction "3_3") (pintype "passive"))
    )
    (net (code "56") (name "unconnected-(IC1-PC4(ADC4{slash}SDA)-Pad27)") (class "Default")
      (node (ref "IC1") (pin "27") (pinfunction "PC4(ADC4/SDA)_27") (pintype "bidirectional"))
    )
    (net (code "57") (name "unconnected-(IC1-PC5(ADC5{slash}SCL)-Pad28)") (class "Default")
      (node (ref "IC1") (pin "28") (pinfunction "PC5(ADC5/SCL)_28") (pintype "bidirectional"))
    )
    (net (code "58") (name "unconnected-(IC2B-~{Q}-Pad8)") (class "Default")
      (node (ref "IC2") (pin "8") (pinfunction "~{Q}_8") (pintype "output"))
    )
    (net (code "59") (name "unconnected-(IC3A-~{Q}-Pad13)") (class "Default")
      (node (ref "IC3") (pin "13") (pinfunction "~{Q}_13") (pintype "output"))
    )
    (net (code "60") (name "unconnected-(IC3B-~{Q}-Pad8)") (class "Default")
      (node (ref "IC3") (pin "8") (pinfunction "~{Q}_8") (pintype "output"))
    )
    (net (code "61") (name "unconnected-(IC4D-Y-Pad6)") (class "Default")
      (node (ref "IC4") (pin "6") (pinfunction "Y_6") (pintype "output"))
    )
    (net (code "62") (name "unconnected-(IC4E-Y-Pad8)") (class "Default")
      (node (ref "IC4") (pin "8") (pinfunction "Y_8") (pintype "output"))
    )
    (net (code "63") (name "unconnected-(IC4F-Y-Pad11)") (class "Default")
      (node (ref "IC4") (pin "11") (pinfunction "Y_11") (pintype "output"))
    )
    (net (code "64") (name "unconnected-(IC5A-~{Q}-Pad4)") (class "Default")
      (node (ref "IC5") (pin "4") (pinfunction "~{Q}_4") (pintype "output"))
    )
    (net (code "65") (name "unconnected-(IC5B-~{Q}-Pad12)") (class "Default")
      (node (ref "IC5") (pin "12") (pinfunction "~{Q}_12") (pintype "output"))
    )
    (net (code "66") (name "unconnected-(IC7B-OUT-Pad7)") (class "Default")
      (node (ref "IC7") (pin "7") (pinfunction "OUT_7") (pintype "output"))
    )
    (net (code "67") (name "unconnected-(R31-S-PadS@1)") (class "Default")
      (node (ref "R31") (pin "S@1") (pinfunction "S_S@1") (pintype "passive"))
    )
    (net (code "68") (name "unconnected-(R72-PadE)") (class "Default")
      (node (ref "R72") (pin "E") (pinfunction "E_E") (pintype "passive"))
    )
    (net (code "69") (name "unconnected-(R72-S-PadS@1)") (class "Default")
      (node (ref "R72") (pin "S@1") (pinfunction "S_S@1") (pintype "passive"))
    )
  )
)
